# Power_Supply.net
KiCad netlist of a schematic drawn in Altium Designer
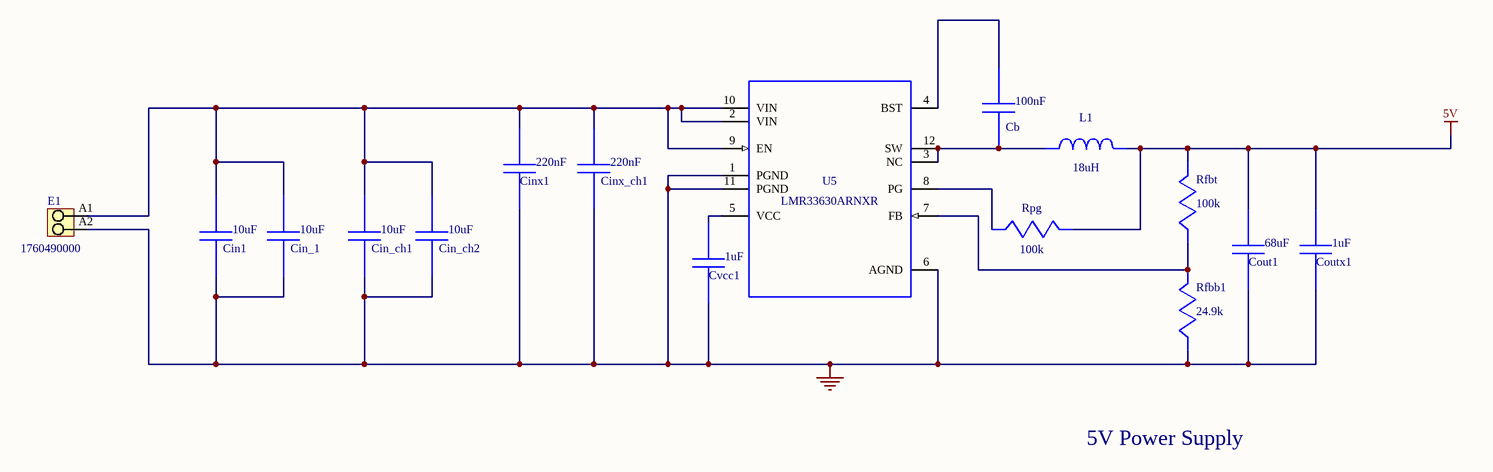
[diagram p0: Power Supply.SchDoc]

(export (version "E")
  (design (tool "Eeschema 10.0.6"))
  (components
    (comp (ref "Cb")
      (value "100nF")
      (footprint "0805")
      (description "CC0805KRX7R9BB10")
      (fields (field (name "MANUFACTURER PART NUMBER") "CC0805KRX7R9BB104"))
      (libsource (lib "TI WEBENCH") (part "Cboot"))
    )
    (comp (ref "Cin1")
      (value "10uF")
      (footprint "0805")
      (description "GRM32ER71J106KA1")
      (fields (field (name "MANUFACTURER PART NUMBER") "GRM32ER71J106KA12L"))
      (libsource (lib "5V Footprints") (part "Cin"))
    )
    (comp (ref "Cinx1")
      (value "220nF")
      (footprint "0603")
      (description "C2012X5R1H224K12")
      (fields (field (name "MANUFACTURER PART NUMBER") "C2012X5R1H224K125AA"))
      (libsource (lib "TI WEBENCH") (part "Cinx"))
    )
    (comp (ref "Cinx_ch1")
      (value "220nF")
      (footprint "0603")
      (description "C2012X5R1H224K12")
      (fields (field (name "MANUFACTURER PART NUMBER") "C2012X5R1H224K125AA"))
      (libsource (lib "TI WEBENCH") (part "Cinx_ch1"))
    )
    (comp (ref "Cin_1")
      (value "10uF")
      (footprint "0805")
      (description "GRM32ER71J106KA1")
      (fields (field (name "MANUFACTURER PART NUMBER") "GRM32ER71J106KA12L"))
      (libsource (lib "TI WEBENCH") (part "Cin_2"))
    )
    (comp (ref "Cin_ch1")
      (value "10uF")
      (footprint "0805")
      (description "GRM32ER71J106KA1")
      (fields (field (name "MANUFACTURER PART NUMBER") "GRM32ER71J106KA12L"))
      (libsource (lib "TI WEBENCH") (part "Cin_ch1"))
    )
    (comp (ref "Cin_ch2")
      (value "10uF")
      (footprint "0805")
      (description "GRM32ER71J106KA1")
      (fields (field (name "MANUFACTURER PART NUMBER") "GRM32ER71J106KA12L"))
      (libsource (lib "TI WEBENCH") (part "Cin_ch1_2"))
    )
    (comp (ref "Cout1")
      (value "68uF")
      (footprint "1210_280")
      (description "C3225X5R0J686M20")
      (fields (field (name "MANUFACTURER PART NUMBER") "C3225X5R0J686M200AC"))
      (libsource (lib "TI WEBENCH") (part "Cout"))
    )
    (comp (ref "Coutx1")
      (value "1uF")
      (footprint "0805")
      (description "GRM21BR71A105KA0")
      (fields (field (name "MANUFACTURER PART NUMBER") "GRM21BR71A105KA01L"))
      (libsource (lib "TI WEBENCH") (part "Coutx"))
    )
    (comp (ref "Cvcc1")
      (value "1uF")
      (footprint "0805")
      (description "C0603C105Z8VACTU")
      (libsource (lib "TI WEBENCH") (part "Cvcc"))
    )
    (comp (ref "E1")
      (value "1760490000")
      (footprint "PM_5_08_90_02")
      (description "OMNIMATE Signal - series PM")
      (fields (field (name "MANUFACTURER") "Weidmueller"))
      (libsource (lib "Altium Content Vault") (part "Terminal_02_1x02"))
    )
    (comp (ref "L1")
      (value "18uH")
      (footprint "CDRH125")
      (description "CDRH125NP-180MC")
      (libsource (lib "TI WEBENCH") (part "L1"))
    )
    (comp (ref "Rfbb1")
      (value "24.9k")
      (footprint "0805")
      (description "ERJ-6ENF2492V")
      (libsource (lib "TI WEBENCH") (part "Rfbb"))
    )
    (comp (ref "Rfbt")
      (value "100k")
      (footprint "0805")
      (description "CRCW0402100KFKED")
      (libsource (lib "TI WEBENCH") (part "Rfbt"))
    )
    (comp (ref "Rpg")
      (value "100k")
      (footprint "0805")
      (description "CRCW0402100KFKED")
      (libsource (lib "TI WEBENCH") (part "Rpg"))
    )
    (comp (ref "U5")
      (value "LMR33630ARNXR")
      (footprint "RNX0012B")
      (fields (field (name "PACKAGEREFERENCE") "LMR33630ARNXR"))
      (libsource (lib "TI WEBENCH") (part "U1"))
    )
  )
  (nets
    (net (code "1") (name "5V") (class "Default")
      (node (ref "Cout1") (pin "1") (pinfunction "1_1") (pintype "passive"))
      (node (ref "Coutx1") (pin "1") (pinfunction "1_1") (pintype "passive"))
      (node (ref "L1") (pin "2") (pinfunction "2_2") (pintype "passive"))
      (node (ref "Rfbt") (pin "1") (pinfunction "1_1") (pintype "passive"))
      (node (ref "Rpg") (pin "1") (pinfunction "1_1") (pintype "passive"))
    )
    (net (code "2") (name "GND") (class "Default")
      (node (ref "Cin1") (pin "2") (pinfunction "2_2") (pintype "passive"))
      (node (ref "Cin_1") (pin "2") (pinfunction "2_2") (pintype "passive"))
      (node (ref "Cin_ch1") (pin "2") (pinfunction "2_2") (pintype "passive"))
      (node (ref "Cin_ch2") (pin "2") (pinfunction "2_2") (pintype "passive"))
      (node (ref "Cinx1") (pin "2") (pinfunction "2_2") (pintype "passive"))
      (node (ref "Cinx_ch1") (pin "2") (pinfunction "2_2") (pintype "passive"))
      (node (ref "Cout1") (pin "2") (pinfunction "2_2") (pintype "passive"))
      (node (ref "Coutx1") (pin "2") (pinfunction "2_2") (pintype "passive"))
      (node (ref "Cvcc1") (pin "2") (pinfunction "2_2") (pintype "passive"))
      (node (ref "E1") (pin "A2") (pinfunction "A2_A2") (pintype "passive"))
      (node (ref "Rfbb1") (pin "2") (pinfunction "2_2") (pintype "passive"))
      (node (ref "U5") (pin "1") (pinfunction "PGND_1") (pintype "power_in"))
      (node (ref "U5") (pin "11") (pinfunction "PGND_11") (pintype "power_in"))
      (node (ref "U5") (pin "6") (pinfunction "AGND_6") (pintype "power_in"))
    )
    (net (code "3") (name "Net-(U5-BST)") (class "Default")
      (node (ref "Cb") (pin "1") (pinfunction "1_1") (pintype "passive"))
      (node (ref "U5") (pin "4") (pinfunction "BST_4") (pintype "passive"))
    )
    (net (code "4") (name "Net-(U5-EN)") (class "Default")
      (node (ref "Cin1") (pin "1") (pinfunction "1_1") (pintype "passive"))
      (node (ref "Cin_1") (pin "1") (pinfunction "1_1") (pintype "passive"))
      (node (ref "Cin_ch1") (pin "1") (pinfunction "1_1") (pintype "passive"))
      (node (ref "Cin_ch2") (pin "1") (pinfunction "1_1") (pintype "passive"))
      (node (ref "Cinx1") (pin "1") (pinfunction "1_1") (pintype "passive"))
      (node (ref "Cinx_ch1") (pin "1") (pinfunction "1_1") (pintype "passive"))
      (node (ref "E1") (pin "A1") (pinfunction "A1_A1") (pintype "passive"))
      (node (ref "U5") (pin "10") (pinfunction "VIN_10") (pintype "power_in"))
      (node (ref "U5") (pin "2") (pinfunction "VIN_2") (pintype "power_in"))
      (node (ref "U5") (pin "9") (pinfunction "EN_9") (pintype "input"))
    )
    (net (code "5") (name "Net-(U5-FB)") (class "Default")
      (node (ref "Rfbb1") (pin "1") (pinfunction "1_1") (pintype "passive"))
      (node (ref "Rfbt") (pin "2") (pinfunction "2_2") (pintype "passive"))
      (node (ref "U5") (pin "7") (pinfunction "FB_7") (pintype "input"))
    )
    (net (code "6") (name "Net-(U5-NC)") (class "Default")
      (node (ref "Cb") (pin "2") (pinfunction "2_2") (pintype "passive"))
      (node (ref "L1") (pin "1") (pinfunction "1_1") (pintype "passive"))
      (node (ref "U5") (pin "12") (pinfunction "SW_12") (pintype "power_in"))
      (node (ref "U5") (pin "3") (pinfunction "NC_3") (pintype "passive"))
    )
    (net (code "7") (name "Net-(U5-PG)") (class "Default")
      (node (ref "Rpg") (pin "2") (pinfunction "2_2") (pintype "passive"))
      (node (ref "U5") (pin "8") (pinfunction "PG_8") (pintype "open_collector"))
    )
    (net (code "8") (name "Net-(U5-VCC)") (class "Default")
      (node (ref "Cvcc1") (pin "1") (pinfunction "1_1") (pintype "passive"))
      (node (ref "U5") (pin "5") (pinfunction "VCC_5") (pintype "power_in"))
    )
  )
)
